# Rele-board.net
KiCad netlist of a schematic drawn in EAGLE
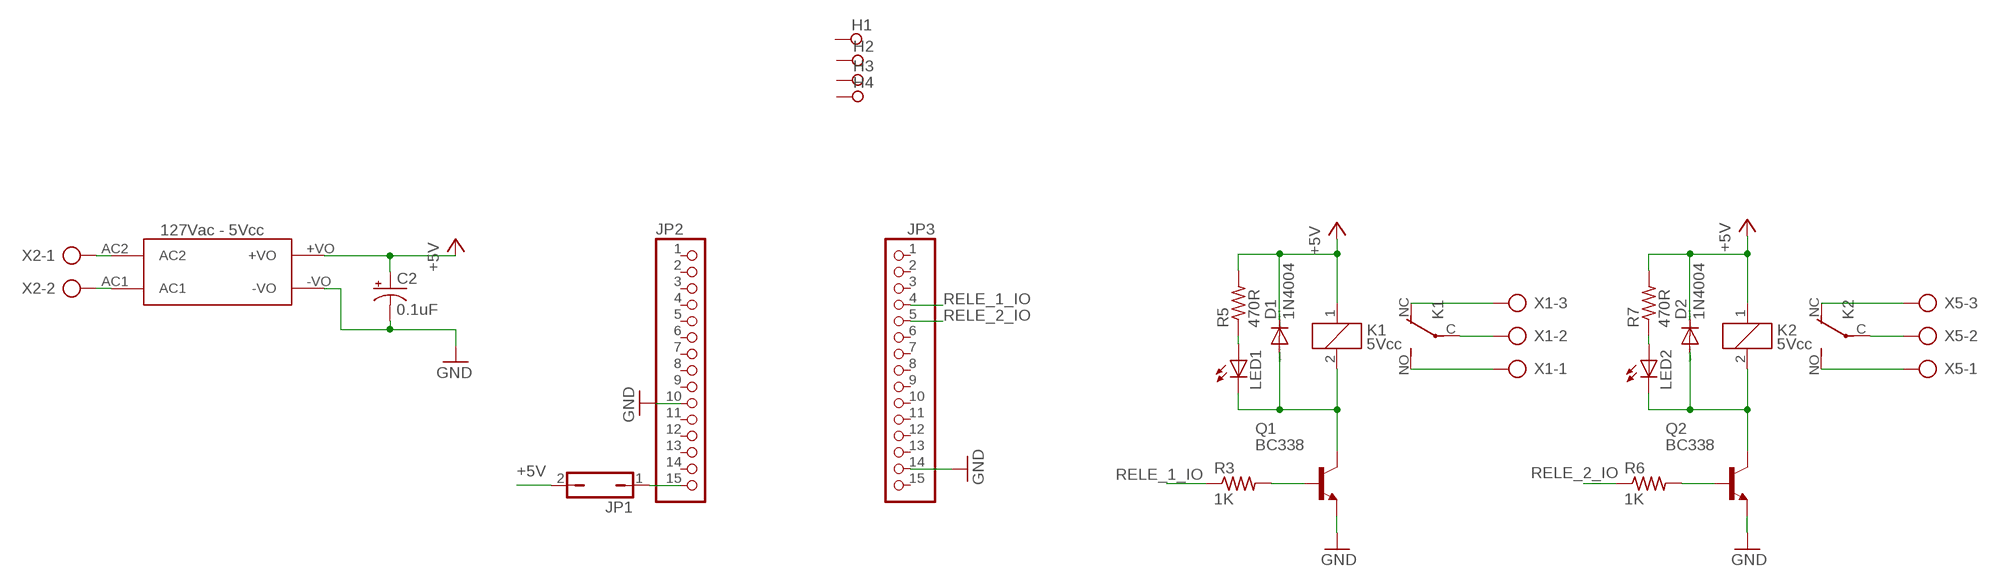
[diagram p0: schematic, sheet 1]

(export (version "E")
  (design (tool "Eeschema 10.0.6"))
  (components
    (comp (ref "C2")
      (value "0.1uF")
      (footprint "eagle-import:E2,5-6")
      (libsource (lib "eagle-import") (part "CPOL-USE2.5-6"))
    )
    (comp (ref "D1")
      (value "1N4004")
      (footprint "eagle-import:DO41-10")
      (libsource (lib "eagle-import") (part "1N4004"))
    )
    (comp (ref "D2")
      (value "1N4004")
      (footprint "eagle-import:DO41-10")
      (libsource (lib "eagle-import") (part "1N4004"))
    )
    (comp (ref "FONTE")
      (value "HLK-PM01")
      (footprint "eagle-import:HLK-PM01")
      (fields (field (name "FONTE") "127Vac - 5Vcc"))
      (libsource (lib "eagle-import") (part "HLK-PM01"))
    )
    (comp (ref "H1")
      (value "SPECIAL_DRILL_0.1000")
      (footprint "eagle-import:PAD_0.1000")
      (libsource (lib "eagle-import") (part "SPECIAL_DRILL_0.1000"))
    )
    (comp (ref "H2")
      (value "SPECIAL_DRILL_0.1000")
      (footprint "eagle-import:PAD_0.1000")
      (libsource (lib "eagle-import") (part "SPECIAL_DRILL_0.1000"))
    )
    (comp (ref "H3")
      (value "SPECIAL_DRILL_0.1000")
      (footprint "eagle-import:PAD_0.1000")
      (libsource (lib "eagle-import") (part "SPECIAL_DRILL_0.1000"))
    )
    (comp (ref "H4")
      (value "SPECIAL_DRILL_0.1000")
      (footprint "eagle-import:PAD_0.1000")
      (libsource (lib "eagle-import") (part "SPECIAL_DRILL_0.1000"))
    )
    (comp (ref "JP1")
      (value "JP1Q")
      (footprint "eagle-import:JP1")
      (libsource (lib "eagle-import") (part "JP1Q"))
    )
    (comp (ref "JP2")
      (value "PINHD-1X15")
      (footprint "eagle-import:1X15")
      (libsource (lib "eagle-import") (part "PINHD-1X15"))
    )
    (comp (ref "JP3")
      (value "PINHD-1X15")
      (footprint "eagle-import:1X15")
      (libsource (lib "eagle-import") (part "PINHD-1X15"))
    )
    (comp (ref "K1")
      (value "5Vcc")
      (footprint "eagle-import:CQ1")
      (libsource (lib "eagle-import") (part "CQ1-12V"))
    )
    (comp (ref "K2")
      (value "5Vcc")
      (footprint "eagle-import:CQ1")
      (libsource (lib "eagle-import") (part "CQ1-12V"))
    )
    (comp (ref "LED1")
      (value "LED3MM")
      (footprint "eagle-import:LED3MM")
      (libsource (lib "eagle-import") (part "LED3MM"))
    )
    (comp (ref "LED2")
      (value "LED3MM")
      (footprint "eagle-import:LED3MM")
      (libsource (lib "eagle-import") (part "LED3MM"))
    )
    (comp (ref "Q1")
      (value "BC338")
      (footprint "eagle-import:TO92-EBC")
      (libsource (lib "eagle-import") (part "BC338"))
    )
    (comp (ref "Q2")
      (value "BC338")
      (footprint "eagle-import:TO92-EBC")
      (libsource (lib "eagle-import") (part "BC338"))
    )
    (comp (ref "R3")
      (value "1K")
      (footprint "eagle-import:0207_10")
      (libsource (lib "eagle-import") (part "R-US_0207/10"))
    )
    (comp (ref "R5")
      (value "470R")
      (footprint "eagle-import:0207_10")
      (libsource (lib "eagle-import") (part "R-US_0207/10"))
    )
    (comp (ref "R6")
      (value "1K")
      (footprint "eagle-import:0207_10")
      (libsource (lib "eagle-import") (part "R-US_0207/10"))
    )
    (comp (ref "R7")
      (value "470R")
      (footprint "eagle-import:0207_10")
      (libsource (lib "eagle-import") (part "R-US_0207/10"))
    )
    (comp (ref "X1")
      (value "AK300/3")
      (footprint "eagle-import:AK300_3")
      (libsource (lib "eagle-import") (part "AK300/3"))
    )
    (comp (ref "X2")
      (value "AK300/2")
      (footprint "eagle-import:AK300_2")
      (libsource (lib "eagle-import") (part "AK300/2"))
    )
    (comp (ref "X5")
      (value "AK300/3")
      (footprint "eagle-import:AK300_3")
      (libsource (lib "eagle-import") (part "AK300/3"))
    )
  )
  (nets
    (net (code "1") (name "+5V") (class "Default")
      (node (ref "C2") (pin "+") (pinfunction "+_+") (pintype "passive"))
      (node (ref "D1") (pin "C") (pinfunction "C_C") (pintype "passive"))
      (node (ref "D2") (pin "C") (pinfunction "C_C") (pintype "passive"))
      (node (ref "FONTE") (pin "+VO") (pinfunction "+VO_+VO") (pintype "bidirectional"))
      (node (ref "JP1") (pin "2") (pinfunction "2_2") (pintype "passive"))
      (node (ref "K1") (pin "1") (pinfunction "1_1") (pintype "passive"))
      (node (ref "K2") (pin "1") (pinfunction "1_1") (pintype "passive"))
      (node (ref "R5") (pin "2") (pinfunction "2_2") (pintype "passive"))
      (node (ref "R7") (pin "2") (pinfunction "2_2") (pintype "passive"))
    )
    (net (code "2") (name "/RELE_1_IO") (class "Default")
      (node (ref "JP3") (pin "4") (pinfunction "4_4") (pintype "passive"))
      (node (ref "R3") (pin "1") (pinfunction "1_1") (pintype "passive"))
    )
    (net (code "3") (name "/RELE_2_IO") (class "Default")
      (node (ref "JP3") (pin "5") (pinfunction "5_5") (pintype "passive"))
      (node (ref "R6") (pin "1") (pinfunction "1_1") (pintype "passive"))
    )
    (net (code "4") (name "GND") (class "Default")
      (node (ref "C2") (pin "-") (pinfunction "-_-") (pintype "passive"))
      (node (ref "FONTE") (pin "-VO") (pinfunction "-VO_-VO") (pintype "bidirectional"))
      (node (ref "JP2") (pin "10") (pinfunction "10_10") (pintype "passive"))
      (node (ref "JP3") (pin "14") (pinfunction "14_14") (pintype "passive"))
      (node (ref "Q1") (pin "E") (pinfunction "E_E") (pintype "passive"))
      (node (ref "Q2") (pin "E") (pinfunction "E_E") (pintype "passive"))
    )
    (net (code "5") (name "Net-(JP1-Pad1)") (class "Default")
      (node (ref "JP1") (pin "1") (pinfunction "1_1") (pintype "passive"))
      (node (ref "JP2") (pin "15") (pinfunction "15_15") (pintype "passive"))
    )
    (net (code "6") (name "Net-(K1B-O)") (class "Default")
      (node (ref "K1") (pin "NC") (pinfunction "O_NC") (pintype "passive"))
      (node (ref "X1") (pin "3") (pinfunction "KL_3") (pintype "passive"))
    )
    (net (code "7") (name "Net-(K1B-P)") (class "Default")
      (node (ref "K1") (pin "C") (pinfunction "P_C") (pintype "passive"))
      (node (ref "X1") (pin "2") (pinfunction "KL_2") (pintype "passive"))
    )
    (net (code "8") (name "Net-(K1B-S)") (class "Default")
      (node (ref "K1") (pin "NO") (pinfunction "S_NO") (pintype "passive"))
      (node (ref "X1") (pin "1") (pinfunction "KL_1") (pintype "passive"))
    )
    (net (code "9") (name "Net-(K2B-O)") (class "Default")
      (node (ref "K2") (pin "NC") (pinfunction "O_NC") (pintype "passive"))
      (node (ref "X5") (pin "3") (pinfunction "KL_3") (pintype "passive"))
    )
    (net (code "10") (name "Net-(K2B-P)") (class "Default")
      (node (ref "K2") (pin "C") (pinfunction "P_C") (pintype "passive"))
      (node (ref "X5") (pin "2") (pinfunction "KL_2") (pintype "passive"))
    )
    (net (code "11") (name "Net-(K2B-S)") (class "Default")
      (node (ref "K2") (pin "NO") (pinfunction "S_NO") (pintype "passive"))
      (node (ref "X5") (pin "1") (pinfunction "KL_1") (pintype "passive"))
    )
    (net (code "12") (name "Net-(LED1-C)") (class "Default")
      (node (ref "D1") (pin "A") (pinfunction "A_A") (pintype "passive"))
      (node (ref "K1") (pin "2") (pinfunction "2_2") (pintype "passive"))
      (node (ref "LED1") (pin "K") (pinfunction "C_K") (pintype "passive"))
      (node (ref "Q1") (pin "C") (pinfunction "C_C") (pintype "passive"))
    )
    (net (code "13") (name "Net-(LED1-PadA)") (class "Default")
      (node (ref "LED1") (pin "A") (pinfunction "A_A") (pintype "passive"))
      (node (ref "R5") (pin "1") (pinfunction "1_1") (pintype "passive"))
    )
    (net (code "14") (name "Net-(LED2-C)") (class "Default")
      (node (ref "D2") (pin "A") (pinfunction "A_A") (pintype "passive"))
      (node (ref "K2") (pin "2") (pinfunction "2_2") (pintype "passive"))
      (node (ref "LED2") (pin "K") (pinfunction "C_K") (pintype "passive"))
      (node (ref "Q2") (pin "C") (pinfunction "C_C") (pintype "passive"))
    )
    (net (code "15") (name "Net-(LED2-PadA)") (class "Default")
      (node (ref "LED2") (pin "A") (pinfunction "A_A") (pintype "passive"))
      (node (ref "R7") (pin "1") (pinfunction "1_1") (pintype "passive"))
    )
    (net (code "16") (name "Net-(Q1-PadB)") (class "Default")
      (node (ref "Q1") (pin "B") (pinfunction "B_B") (pintype "passive"))
      (node (ref "R3") (pin "2") (pinfunction "2_2") (pintype "passive"))
    )
    (net (code "17") (name "Net-(Q2-PadB)") (class "Default")
      (node (ref "Q2") (pin "B") (pinfunction "B_B") (pintype "passive"))
      (node (ref "R6") (pin "2") (pinfunction "2_2") (pintype "passive"))
    )
    (net (code "18") (name "Net-(X2A-KL)") (class "Default")
      (node (ref "FONTE") (pin "AC2") (pinfunction "AC2_AC2") (pintype "bidirectional"))
      (node (ref "X2") (pin "1") (pinfunction "KL_1") (pintype "passive"))
    )
    (net (code "19") (name "Net-(X2B-KL)") (class "Default")
      (node (ref "FONTE") (pin "AC1") (pinfunction "AC1_AC1") (pintype "bidirectional"))
      (node (ref "X2") (pin "2") (pinfunction "KL_2") (pintype "passive"))
    )
    (net (code "20") (name "unconnected-(H1-Pad1)") (class "Default")
      (node (ref "H1") (pin "1") (pinfunction "1_1") (pintype "passive"))
    )
    (net (code "21") (name "unconnected-(H2-Pad1)") (class "Default")
      (node (ref "H2") (pin "1") (pinfunction "1_1") (pintype "passive"))
    )
    (net (code "22") (name "unconnected-(H3-Pad1)") (class "Default")
      (node (ref "H3") (pin "1") (pinfunction "1_1") (pintype "passive"))
    )
    (net (code "23") (name "unconnected-(H4-Pad1)") (class "Default")
      (node (ref "H4") (pin "1") (pinfunction "1_1") (pintype "passive"))
    )
    (net (code "24") (name "unconnected-(JP2-Pad1)") (class "Default")
      (node (ref "JP2") (pin "1") (pinfunction "1_1") (pintype "passive"))
    )
    (net (code "25") (name "unconnected-(JP2-Pad2)") (class "Default")
      (node (ref "JP2") (pin "2") (pinfunction "2_2") (pintype "passive"))
    )
    (net (code "26") (name "unconnected-(JP2-Pad3)") (class "Default")
      (node (ref "JP2") (pin "3") (pinfunction "3_3") (pintype "passive"))
    )
    (net (code "27") (name "unconnected-(JP2-Pad4)") (class "Default")
      (node (ref "JP2") (pin "4") (pinfunction "4_4") (pintype "passive"))
    )
    (net (code "28") (name "unconnected-(JP2-Pad5)") (class "Default")
      (node (ref "JP2") (pin "5") (pinfunction "5_5") (pintype "passive"))
    )
    (net (code "29") (name "unconnected-(JP2-Pad6)") (class "Default")
      (node (ref "JP2") (pin "6") (pinfunction "6_6") (pintype "passive"))
    )
    (net (code "30") (name "unconnected-(JP2-Pad7)") (class "Default")
      (node (ref "JP2") (pin "7") (pinfunction "7_7") (pintype "passive"))
    )
    (net (code "31") (name "unconnected-(JP2-Pad8)") (class "Default")
      (node (ref "JP2") (pin "8") (pinfunction "8_8") (pintype "passive"))
    )
    (net (code "32") (name "unconnected-(JP2-Pad9)") (class "Default")
      (node (ref "JP2") (pin "9") (pinfunction "9_9") (pintype "passive"))
    )
    (net (code "33") (name "unconnected-(JP2-Pad11)") (class "Default")
      (node (ref "JP2") (pin "11") (pinfunction "11_11") (pintype "passive"))
    )
    (net (code "34") (name "unconnected-(JP2-Pad12)") (class "Default")
      (node (ref "JP2") (pin "12") (pinfunction "12_12") (pintype "passive"))
    )
    (net (code "35") (name "unconnected-(JP2-Pad13)") (class "Default")
      (node (ref "JP2") (pin "13") (pinfunction "13_13") (pintype "passive"))
    )
    (net (code "36") (name "unconnected-(JP2-Pad14)") (class "Default")
      (node (ref "JP2") (pin "14") (pinfunction "14_14") (pintype "passive"))
    )
    (net (code "37") (name "unconnected-(JP3-Pad1)") (class "Default")
      (node (ref "JP3") (pin "1") (pinfunction "1_1") (pintype "passive"))
    )
    (net (code "38") (name "unconnected-(JP3-Pad2)") (class "Default")
      (node (ref "JP3") (pin "2") (pinfunction "2_2") (pintype "passive"))
    )
    (net (code "39") (name "unconnected-(JP3-Pad3)") (class "Default")
      (node (ref "JP3") (pin "3") (pinfunction "3_3") (pintype "passive"))
    )
    (net (code "40") (name "unconnected-(JP3-Pad6)") (class "Default")
      (node (ref "JP3") (pin "6") (pinfunction "6_6") (pintype "passive"))
    )
    (net (code "41") (name "unconnected-(JP3-Pad7)") (class "Default")
      (node (ref "JP3") (pin "7") (pinfunction "7_7") (pintype "passive"))
    )
    (net (code "42") (name "unconnected-(JP3-Pad8)") (class "Default")
      (node (ref "JP3") (pin "8") (pinfunction "8_8") (pintype "passive"))
    )
    (net (code "43") (name "unconnected-(JP3-Pad9)") (class "Default")
      (node (ref "JP3") (pin "9") (pinfunction "9_9") (pintype "passive"))
    )
    (net (code "44") (name "unconnected-(JP3-Pad10)") (class "Default")
      (node (ref "JP3") (pin "10") (pinfunction "10_10") (pintype "passive"))
    )
    (net (code "45") (name "unconnected-(JP3-Pad11)") (class "Default")
      (node (ref "JP3") (pin "11") (pinfunction "11_11") (pintype "passive"))
    )
    (net (code "46") (name "unconnected-(JP3-Pad12)") (class "Default")
      (node (ref "JP3") (pin "12") (pinfunction "12_12") (pintype "passive"))
    )
    (net (code "47") (name "unconnected-(JP3-Pad13)") (class "Default")
      (node (ref "JP3") (pin "13") (pinfunction "13_13") (pintype "passive"))
    )
    (net (code "48") (name "unconnected-(JP3-Pad15)") (class "Default")
      (node (ref "JP3") (pin "15") (pinfunction "15_15") (pintype "passive"))
    )
  )
)
